# ArduinoUnoShield.net
KiCad netlist of a schematic drawn in Altium Designer
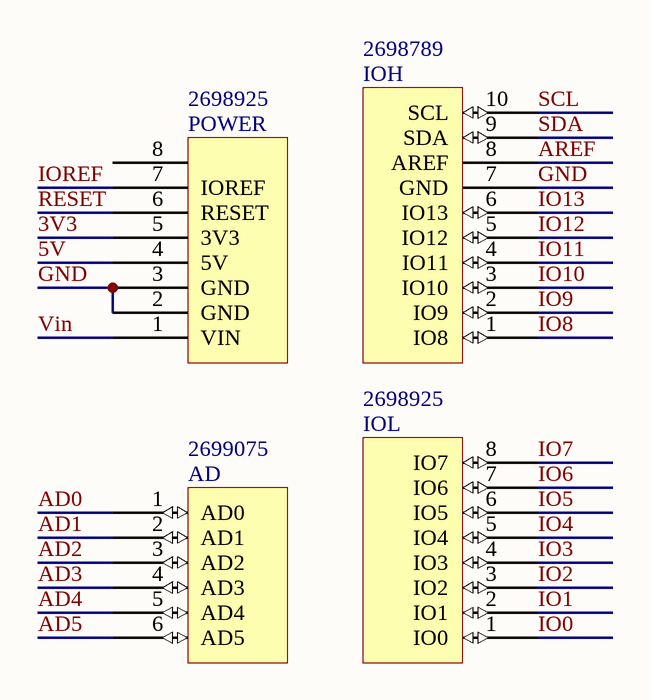
[diagram p0: ArduinoUnoShield.SchDoc]

(export (version "E")
  (design (tool "Eeschema 10.0.6"))
  (components
    (comp (ref "AD")
      (value "AD")
      (footprint "Header:Header 6x1 8.5mm")
      (fields (field (name "SUPPLIER PART NUMBER 4") "2699075"))
      (libsource (lib "Header") (part "AD"))
    )
    (comp (ref "IOH")
      (value "IOH")
      (footprint "Header:Header 10x1 8.5mm")
      (fields (field (name "SUPPLIER PART NUMBER 3") "2698789"))
      (libsource (lib "Header") (part "IOH"))
    )
    (comp (ref "IOL")
      (value "IOL")
      (footprint "Header 8x1 8.5mm")
      (fields (field (name "SUPPLIER PART NUMBER 4") "2698925"))
      (libsource (lib "Header") (part "IOL"))
    )
    (comp (ref "POWER")
      (value "POWER_UNO")
      (footprint "Header 8x1 8.5mm")
      (fields (field (name "SUPPLIER PART NUMBER 4") "2698925"))
      (libsource (lib "Header") (part "POWER_UNO"))
    )
  )
  (nets
    (net (code "1") (name "/3V3") (class "Default")
      (node (ref "POWER") (pin "5") (pinfunction "3V3_5") (pintype "power_in"))
    )
    (net (code "2") (name "/5V") (class "Default")
      (node (ref "POWER") (pin "4") (pinfunction "5V_4") (pintype "power_in"))
    )
    (net (code "4") (name "/AD0") (class "Default")
      (node (ref "AD") (pin "1") (pinfunction "AD0_1") (pintype "bidirectional"))
    )
    (net (code "5") (name "/AD1") (class "Default")
      (node (ref "AD") (pin "2") (pinfunction "AD1_2") (pintype "bidirectional"))
    )
    (net (code "6") (name "/AD2") (class "Default")
      (node (ref "AD") (pin "3") (pinfunction "AD2_3") (pintype "bidirectional"))
    )
    (net (code "7") (name "/AD3") (class "Default")
      (node (ref "AD") (pin "4") (pinfunction "AD3_4") (pintype "bidirectional"))
    )
    (net (code "8") (name "/AD4") (class "Default")
      (node (ref "AD") (pin "5") (pinfunction "AD4_5") (pintype "bidirectional"))
    )
    (net (code "9") (name "/AD5") (class "Default")
      (node (ref "AD") (pin "6") (pinfunction "AD5_6") (pintype "bidirectional"))
    )
    (net (code "10") (name "/AREF") (class "Default")
      (node (ref "IOH") (pin "8") (pinfunction "AREF_8") (pintype "passive"))
    )
    (net (code "11") (name "/GND") (class "Default")
      (node (ref "IOH") (pin "7") (pinfunction "GND_7") (pintype "power_in"))
      (node (ref "POWER") (pin "2") (pinfunction "GND_2") (pintype "power_in"))
      (node (ref "POWER") (pin "3") (pinfunction "GND_3") (pintype "power_in"))
    )
    (net (code "12") (name "/IO0") (class "Default")
      (node (ref "IOL") (pin "1") (pinfunction "IO0_1") (pintype "bidirectional"))
    )
    (net (code "13") (name "/IO1") (class "Default")
      (node (ref "IOL") (pin "2") (pinfunction "IO1_2") (pintype "bidirectional"))
    )
    (net (code "14") (name "/IO2") (class "Default")
      (node (ref "IOL") (pin "3") (pinfunction "IO2_3") (pintype "bidirectional"))
    )
    (net (code "15") (name "/IO3") (class "Default")
      (node (ref "IOL") (pin "4") (pinfunction "IO3_4") (pintype "bidirectional"))
    )
    (net (code "16") (name "/IO4") (class "Default")
      (node (ref "IOL") (pin "5") (pinfunction "IO4_5") (pintype "bidirectional"))
    )
    (net (code "17") (name "/IO5") (class "Default")
      (node (ref "IOL") (pin "6") (pinfunction "IO5_6") (pintype "bidirectional"))
    )
    (net (code "18") (name "/IO6") (class "Default")
      (node (ref "IOL") (pin "7") (pinfunction "IO6_7") (pintype "bidirectional"))
    )
    (net (code "19") (name "/IO7") (class "Default")
      (node (ref "IOL") (pin "8") (pinfunction "IO7_8") (pintype "bidirectional"))
    )
    (net (code "20") (name "/IO8") (class "Default")
      (node (ref "IOH") (pin "1") (pinfunction "IO8_1") (pintype "bidirectional"))
    )
    (net (code "21") (name "/IO9") (class "Default")
      (node (ref "IOH") (pin "2") (pinfunction "IO9_2") (pintype "bidirectional"))
    )
    (net (code "22") (name "/IO10") (class "Default")
      (node (ref "IOH") (pin "3") (pinfunction "IO10_3") (pintype "bidirectional"))
    )
    (net (code "23") (name "/IO11") (class "Default")
      (node (ref "IOH") (pin "4") (pinfunction "IO11_4") (pintype "bidirectional"))
    )
    (net (code "24") (name "/IO12") (class "Default")
      (node (ref "IOH") (pin "5") (pinfunction "IO12_5") (pintype "bidirectional"))
    )
    (net (code "25") (name "/IO13") (class "Default")
      (node (ref "IOH") (pin "6") (pinfunction "IO13_6") (pintype "bidirectional"))
    )
    (net (code "26") (name "/IOREF") (class "Default")
      (node (ref "POWER") (pin "7") (pinfunction "IOREF_7") (pintype "power_in"))
    )
    (net (code "27") (name "/RESET") (class "Default")
      (node (ref "POWER") (pin "6") (pinfunction "RESET_6") (pintype "passive"))
    )
    (net (code "28") (name "/SCL") (class "Default")
      (node (ref "IOH") (pin "10") (pinfunction "SCL_10") (pintype "bidirectional"))
    )
    (net (code "29") (name "/SDA") (class "Default")
      (node (ref "IOH") (pin "9") (pinfunction "SDA_9") (pintype "bidirectional"))
    )
    (net (code "30") (name "/Vin") (class "Default")
      (node (ref "POWER") (pin "1") (pinfunction "VIN_1") (pintype "power_in"))
    )
    (net (code "31") (name "unconnected-(POWER-Pad8)") (class "Default")
      (node (ref "POWER") (pin "8") (pintype "passive"))
    )
  )
)
